# schematics.net
KiCad netlist of a schematic drawn in EAGLE
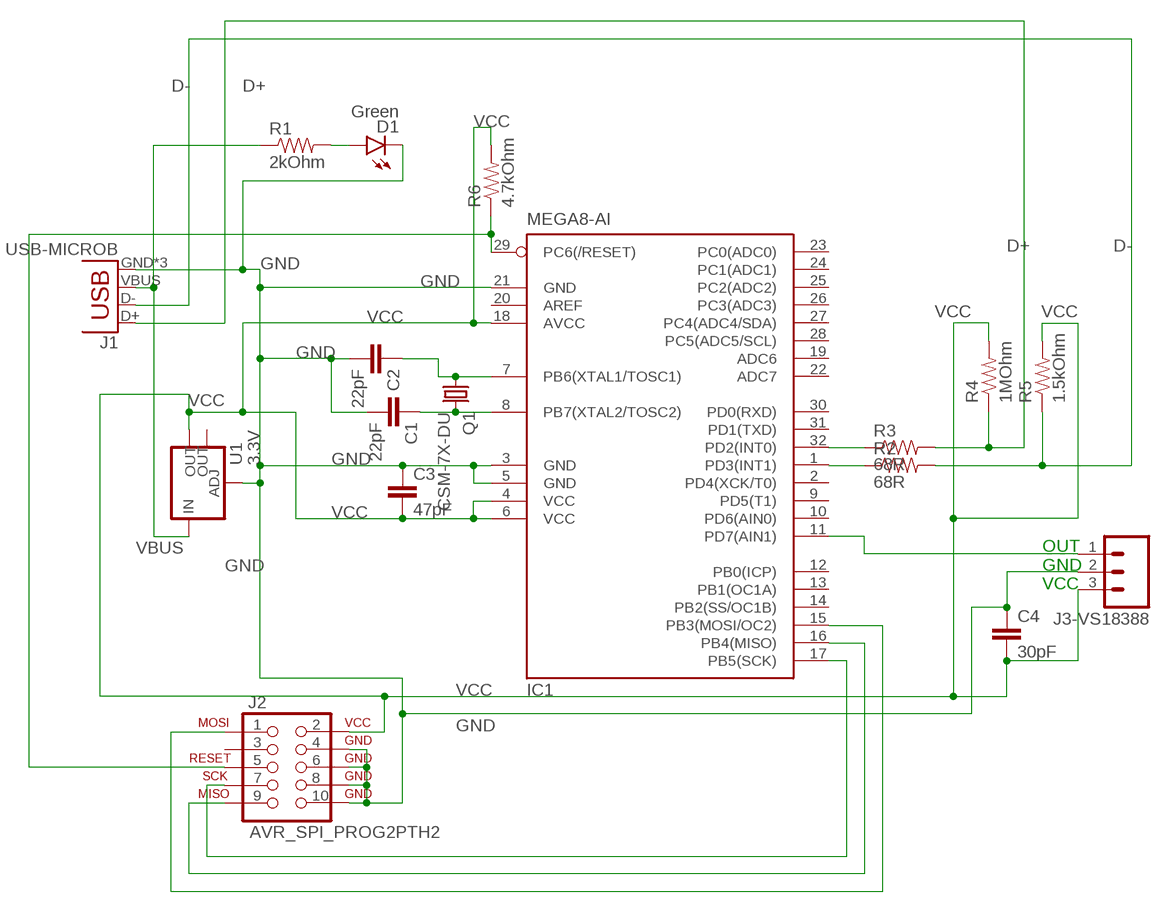
[diagram p0: schematic, sheet 1]

(export (version "E")
  (design (tool "Eeschema 10.0.6"))
  (components
    (comp (ref "C1")
      (value "22pF")
      (footprint "eagle-import:1206")
      (libsource (lib "eagle-import") (part "2.2UF-CERCAP-10009"))
    )
    (comp (ref "C2")
      (value "22pF")
      (footprint "eagle-import:1206")
      (libsource (lib "eagle-import") (part "2.2UF-CERCAP-10009"))
    )
    (comp (ref "C3")
      (value "47pF")
      (footprint "eagle-import:1206")
      (libsource (lib "eagle-import") (part "2.2UF-CERCAP-10009"))
    )
    (comp (ref "C4")
      (value "30pF")
      (footprint "eagle-import:1206")
      (libsource (lib "eagle-import") (part "2.2UF-CERCAP-10009"))
    )
    (comp (ref "D1")
      (value "Green")
      (footprint "eagle-import:LED-1206")
      (libsource (lib "eagle-import") (part "LED1206"))
    )
    (comp (ref "IC1")
      (value "MEGA8-AI")
      (footprint "eagle-import:TQFP32-08")
      (fields (field (name "MPN") "ATMEGA8-16AU"))
      (libsource (lib "eagle-import") (part "MEGA8-AI"))
    )
    (comp (ref "J1")
      (value "USB-MICROB")
      (footprint "eagle-import:USB-MICROB")
      (libsource (lib "eagle-import") (part "USB-MICROB"))
    )
    (comp (ref "J2")
      (value "AVR_SPI_PROG2PTH2")
      (footprint "eagle-import:2X5-SHROUDED")
      (libsource (lib "eagle-import") (part "AVR_SPI_PROG2PTH2"))
    )
    (comp (ref "J3-VS18388")
      (value "M03PTH")
      (footprint "eagle-import:1X03")
      (libsource (lib "eagle-import") (part "M03PTH"))
    )
    (comp (ref "Q1")
      (value "CSM-7X-DU")
      (footprint "eagle-import:CSM-7X-DU")
      (libsource (lib "eagle-import") (part "CSM-7X-DU"))
    )
    (comp (ref "R1")
      (value "2kOhm")
      (footprint "eagle-import:1206")
      (libsource (lib "eagle-import") (part "RESISTOR1206"))
    )
    (comp (ref "R2")
      (value "68R")
      (footprint "eagle-import:1206")
      (libsource (lib "eagle-import") (part "RESISTOR1206"))
    )
    (comp (ref "R3")
      (value "68R")
      (footprint "eagle-import:1206")
      (libsource (lib "eagle-import") (part "RESISTOR1206"))
    )
    (comp (ref "R4")
      (value "1MOhm")
      (footprint "eagle-import:1206")
      (libsource (lib "eagle-import") (part "RESISTOR1206"))
    )
    (comp (ref "R5")
      (value "1.5kOhm")
      (footprint "eagle-import:1206")
      (libsource (lib "eagle-import") (part "RESISTOR1206"))
    )
    (comp (ref "R6")
      (value "4.7kOhm")
      (footprint "eagle-import:1206")
      (libsource (lib "eagle-import") (part "RESISTOR1206"))
    )
    (comp (ref "U1")
      (value "3.3V")
      (footprint "eagle-import:SOT223")
      (libsource (lib "eagle-import") (part "V_REG_LM1117SOT223"))
    )
  )
  (nets
    (net (code "1") (name "/D+") (class "Default")
      (node (ref "J1") (pin "D+") (pinfunction "D+_D+") (pintype "bidirectional"))
      (node (ref "R3") (pin "2") (pinfunction "2_2") (pintype "passive"))
      (node (ref "R4") (pin "1") (pinfunction "1_1") (pintype "passive"))
    )
    (net (code "2") (name "/D-") (class "Default")
      (node (ref "J1") (pin "D-") (pinfunction "D-_D-") (pintype "bidirectional"))
      (node (ref "R2") (pin "2") (pinfunction "2_2") (pintype "passive"))
      (node (ref "R5") (pin "1") (pinfunction "1_1") (pintype "passive"))
    )
    (net (code "3") (name "/GND") (class "Default")
      (node (ref "C1") (pin "2") (pinfunction "2_2") (pintype "passive"))
      (node (ref "C2") (pin "2") (pinfunction "2_2") (pintype "passive"))
      (node (ref "C3") (pin "1") (pinfunction "1_1") (pintype "passive"))
      (node (ref "C4") (pin "1") (pinfunction "1_1") (pintype "passive"))
      (node (ref "D1") (pin "C") (pinfunction "C_C") (pintype "passive"))
      (node (ref "IC1") (pin "21") (pinfunction "GND_21") (pintype "power_in"))
      (node (ref "IC1") (pin "3") (pinfunction "GND_3") (pintype "power_in"))
      (node (ref "IC1") (pin "5") (pinfunction "GND_5") (pintype "power_in"))
      (node (ref "J1") (pin "GND") (pinfunction "GND_GND") (pintype "bidirectional"))
      (node (ref "J1") (pin "MT1") (pinfunction "GND_MT1") (pintype "bidirectional"))
      (node (ref "J1") (pin "MT2") (pinfunction "GND_MT2") (pintype "bidirectional"))
      (node (ref "J2") (pin "10") (pinfunction "GND_10") (pintype "power_in"))
      (node (ref "J2") (pin "4") (pinfunction "GND_4") (pintype "power_in"))
      (node (ref "J2") (pin "6") (pinfunction "GND_6") (pintype "power_in"))
      (node (ref "J2") (pin "8") (pinfunction "GND_8") (pintype "power_in"))
      (node (ref "J3-VS18388") (pin "2") (pinfunction "2_2") (pintype "passive"))
      (node (ref "U1") (pin "1") (pinfunction "ADJ_1") (pintype "input"))
    )
    (net (code "4") (name "/VBUS") (class "Default")
      (node (ref "J1") (pin "VBUS") (pinfunction "VBUS_VBUS") (pintype "bidirectional"))
      (node (ref "R1") (pin "1") (pinfunction "1_1") (pintype "passive"))
      (node (ref "U1") (pin "3") (pinfunction "IN_3") (pintype "input"))
    )
    (net (code "5") (name "/VCC") (class "Default")
      (node (ref "C3") (pin "2") (pinfunction "2_2") (pintype "passive"))
      (node (ref "C4") (pin "2") (pinfunction "2_2") (pintype "passive"))
      (node (ref "IC1") (pin "18") (pinfunction "AVCC_18") (pintype "power_in"))
      (node (ref "IC1") (pin "4") (pinfunction "VCC_4") (pintype "power_in"))
      (node (ref "IC1") (pin "6") (pinfunction "VCC_6") (pintype "power_in"))
      (node (ref "J2") (pin "2") (pinfunction "VCC_2") (pintype "power_in"))
      (node (ref "J3-VS18388") (pin "3") (pinfunction "3_3") (pintype "passive"))
      (node (ref "R4") (pin "2") (pinfunction "2_2") (pintype "passive"))
      (node (ref "R5") (pin "2") (pinfunction "2_2") (pintype "passive"))
      (node (ref "R6") (pin "2") (pinfunction "2_2") (pintype "passive"))
      (node (ref "U1") (pin "2") (pinfunction "OUT_2") (pintype "output"))
    )
    (net (code "6") (name "Net-(D1-PadA)") (class "Default")
      (node (ref "D1") (pin "A") (pinfunction "A_A") (pintype "passive"))
      (node (ref "R1") (pin "2") (pinfunction "2_2") (pintype "passive"))
    )
    (net (code "7") (name "Net-(IC1-PB3(MOSI{slash}OC2))") (class "Default")
      (node (ref "IC1") (pin "15") (pinfunction "PB3(MOSI/OC2)_15") (pintype "bidirectional"))
      (node (ref "J2") (pin "1") (pinfunction "MOSI_1") (pintype "passive"))
    )
    (net (code "8") (name "Net-(IC1-PB4(MISO))") (class "Default")
      (node (ref "IC1") (pin "16") (pinfunction "PB4(MISO)_16") (pintype "bidirectional"))
      (node (ref "J2") (pin "9") (pinfunction "MISO_9") (pintype "passive"))
    )
    (net (code "9") (name "Net-(IC1-PB5(SCK))") (class "Default")
      (node (ref "IC1") (pin "17") (pinfunction "PB5(SCK)_17") (pintype "bidirectional"))
      (node (ref "J2") (pin "7") (pinfunction "SCK_7") (pintype "passive"))
    )
    (net (code "10") (name "Net-(IC1-PB6(XTAL1{slash}TOSC1))") (class "Default")
      (node (ref "C2") (pin "1") (pinfunction "1_1") (pintype "passive"))
      (node (ref "IC1") (pin "7") (pinfunction "PB6(XTAL1/TOSC1)_7") (pintype "bidirectional"))
      (node (ref "Q1") (pin "1") (pinfunction "1_1") (pintype "passive"))
    )
    (net (code "11") (name "Net-(IC1-PB7(XTAL2{slash}TOSC2))") (class "Default")
      (node (ref "C1") (pin "1") (pinfunction "1_1") (pintype "passive"))
      (node (ref "IC1") (pin "8") (pinfunction "PB7(XTAL2/TOSC2)_8") (pintype "bidirectional"))
      (node (ref "Q1") (pin "2") (pinfunction "2_2") (pintype "passive"))
    )
    (net (code "12") (name "Net-(IC1-PC6({slash}RESET))") (class "Default")
      (node (ref "IC1") (pin "29") (pinfunction "PC6(/RESET)_29") (pintype "bidirectional"))
      (node (ref "J2") (pin "5") (pinfunction "RESET_5") (pintype "passive"))
      (node (ref "R6") (pin "1") (pinfunction "1_1") (pintype "passive"))
    )
    (net (code "13") (name "Net-(IC1-PD2(INT0))") (class "Default")
      (node (ref "IC1") (pin "32") (pinfunction "PD2(INT0)_32") (pintype "bidirectional"))
      (node (ref "R3") (pin "1") (pinfunction "1_1") (pintype "passive"))
    )
    (net (code "14") (name "Net-(IC1-PD3(INT1))") (class "Default")
      (node (ref "IC1") (pin "1") (pinfunction "PD3(INT1)_1") (pintype "bidirectional"))
      (node (ref "R2") (pin "1") (pinfunction "1_1") (pintype "passive"))
    )
    (net (code "15") (name "Net-(IC1-PD7(AIN1))") (class "Default")
      (node (ref "IC1") (pin "11") (pinfunction "PD7(AIN1)_11") (pintype "bidirectional"))
      (node (ref "J3-VS18388") (pin "1") (pinfunction "1_1") (pintype "passive"))
    )
    (net (code "16") (name "unconnected-(IC1-ADC6-Pad19)") (class "Default")
      (node (ref "IC1") (pin "19") (pinfunction "ADC6_19") (pintype "bidirectional"))
    )
    (net (code "17") (name "unconnected-(IC1-ADC7-Pad22)") (class "Default")
      (node (ref "IC1") (pin "22") (pinfunction "ADC7_22") (pintype "bidirectional"))
    )
    (net (code "18") (name "unconnected-(IC1-AREF-Pad20)") (class "Default")
      (node (ref "IC1") (pin "20") (pinfunction "AREF_20") (pintype "passive"))
    )
    (net (code "19") (name "unconnected-(IC1-PB0(ICP)-Pad12)") (class "Default")
      (node (ref "IC1") (pin "12") (pinfunction "PB0(ICP)_12") (pintype "bidirectional"))
    )
    (net (code "20") (name "unconnected-(IC1-PB1(OC1A)-Pad13)") (class "Default")
      (node (ref "IC1") (pin "13") (pinfunction "PB1(OC1A)_13") (pintype "bidirectional"))
    )
    (net (code "21") (name "unconnected-(IC1-PB2(SS{slash}OC1B)-Pad14)") (class "Default")
      (node (ref "IC1") (pin "14") (pinfunction "PB2(SS/OC1B)_14") (pintype "bidirectional"))
    )
    (net (code "22") (name "unconnected-(IC1-PC0(ADC0)-Pad23)") (class "Default")
      (node (ref "IC1") (pin "23") (pinfunction "PC0(ADC0)_23") (pintype "bidirectional"))
    )
    (net (code "23") (name "unconnected-(IC1-PC1(ADC1)-Pad24)") (class "Default")
      (node (ref "IC1") (pin "24") (pinfunction "PC1(ADC1)_24") (pintype "bidirectional"))
    )
    (net (code "24") (name "unconnected-(IC1-PC2(ADC2)-Pad25)") (class "Default")
      (node (ref "IC1") (pin "25") (pinfunction "PC2(ADC2)_25") (pintype "bidirectional"))
    )
    (net (code "25") (name "unconnected-(IC1-PC3(ADC3)-Pad26)") (class "Default")
      (node (ref "IC1") (pin "26") (pinfunction "PC3(ADC3)_26") (pintype "bidirectional"))
    )
    (net (code "26") (name "unconnected-(IC1-PC4(ADC4{slash}SDA)-Pad27)") (class "Default")
      (node (ref "IC1") (pin "27") (pinfunction "PC4(ADC4/SDA)_27") (pintype "bidirectional"))
    )
    (net (code "27") (name "unconnected-(IC1-PC5(ADC5{slash}SCL)-Pad28)") (class "Default")
      (node (ref "IC1") (pin "28") (pinfunction "PC5(ADC5/SCL)_28") (pintype "bidirectional"))
    )
    (net (code "28") (name "unconnected-(IC1-PD0(RXD)-Pad30)") (class "Default")
      (node (ref "IC1") (pin "30") (pinfunction "PD0(RXD)_30") (pintype "bidirectional"))
    )
    (net (code "29") (name "unconnected-(IC1-PD1(TXD)-Pad31)") (class "Default")
      (node (ref "IC1") (pin "31") (pinfunction "PD1(TXD)_31") (pintype "bidirectional"))
    )
    (net (code "30") (name "unconnected-(IC1-PD4(XCK{slash}T0)-Pad2)") (class "Default")
      (node (ref "IC1") (pin "2") (pinfunction "PD4(XCK/T0)_2") (pintype "bidirectional"))
    )
    (net (code "31") (name "unconnected-(IC1-PD5(T1)-Pad9)") (class "Default")
      (node (ref "IC1") (pin "9") (pinfunction "PD5(T1)_9") (pintype "bidirectional"))
    )
    (net (code "32") (name "unconnected-(IC1-PD6(AIN0)-Pad10)") (class "Default")
      (node (ref "IC1") (pin "10") (pinfunction "PD6(AIN0)_10") (pintype "bidirectional"))
    )
    (net (code "33") (name "unconnected-(J2-NC-Pad3)") (class "Default")
      (node (ref "J2") (pin "3") (pinfunction "NC_3") (pintype "no_connect"))
    )
    (net (code "34") (name "unconnected-(U1-OUT-Pad4)") (class "Default")
      (node (ref "U1") (pin "4") (pinfunction "OUT_4") (pintype "output"))
    )
  )
)
